# RMR-AVR-ISP-Shield.net
KiCad netlist of a schematic drawn in EAGLE
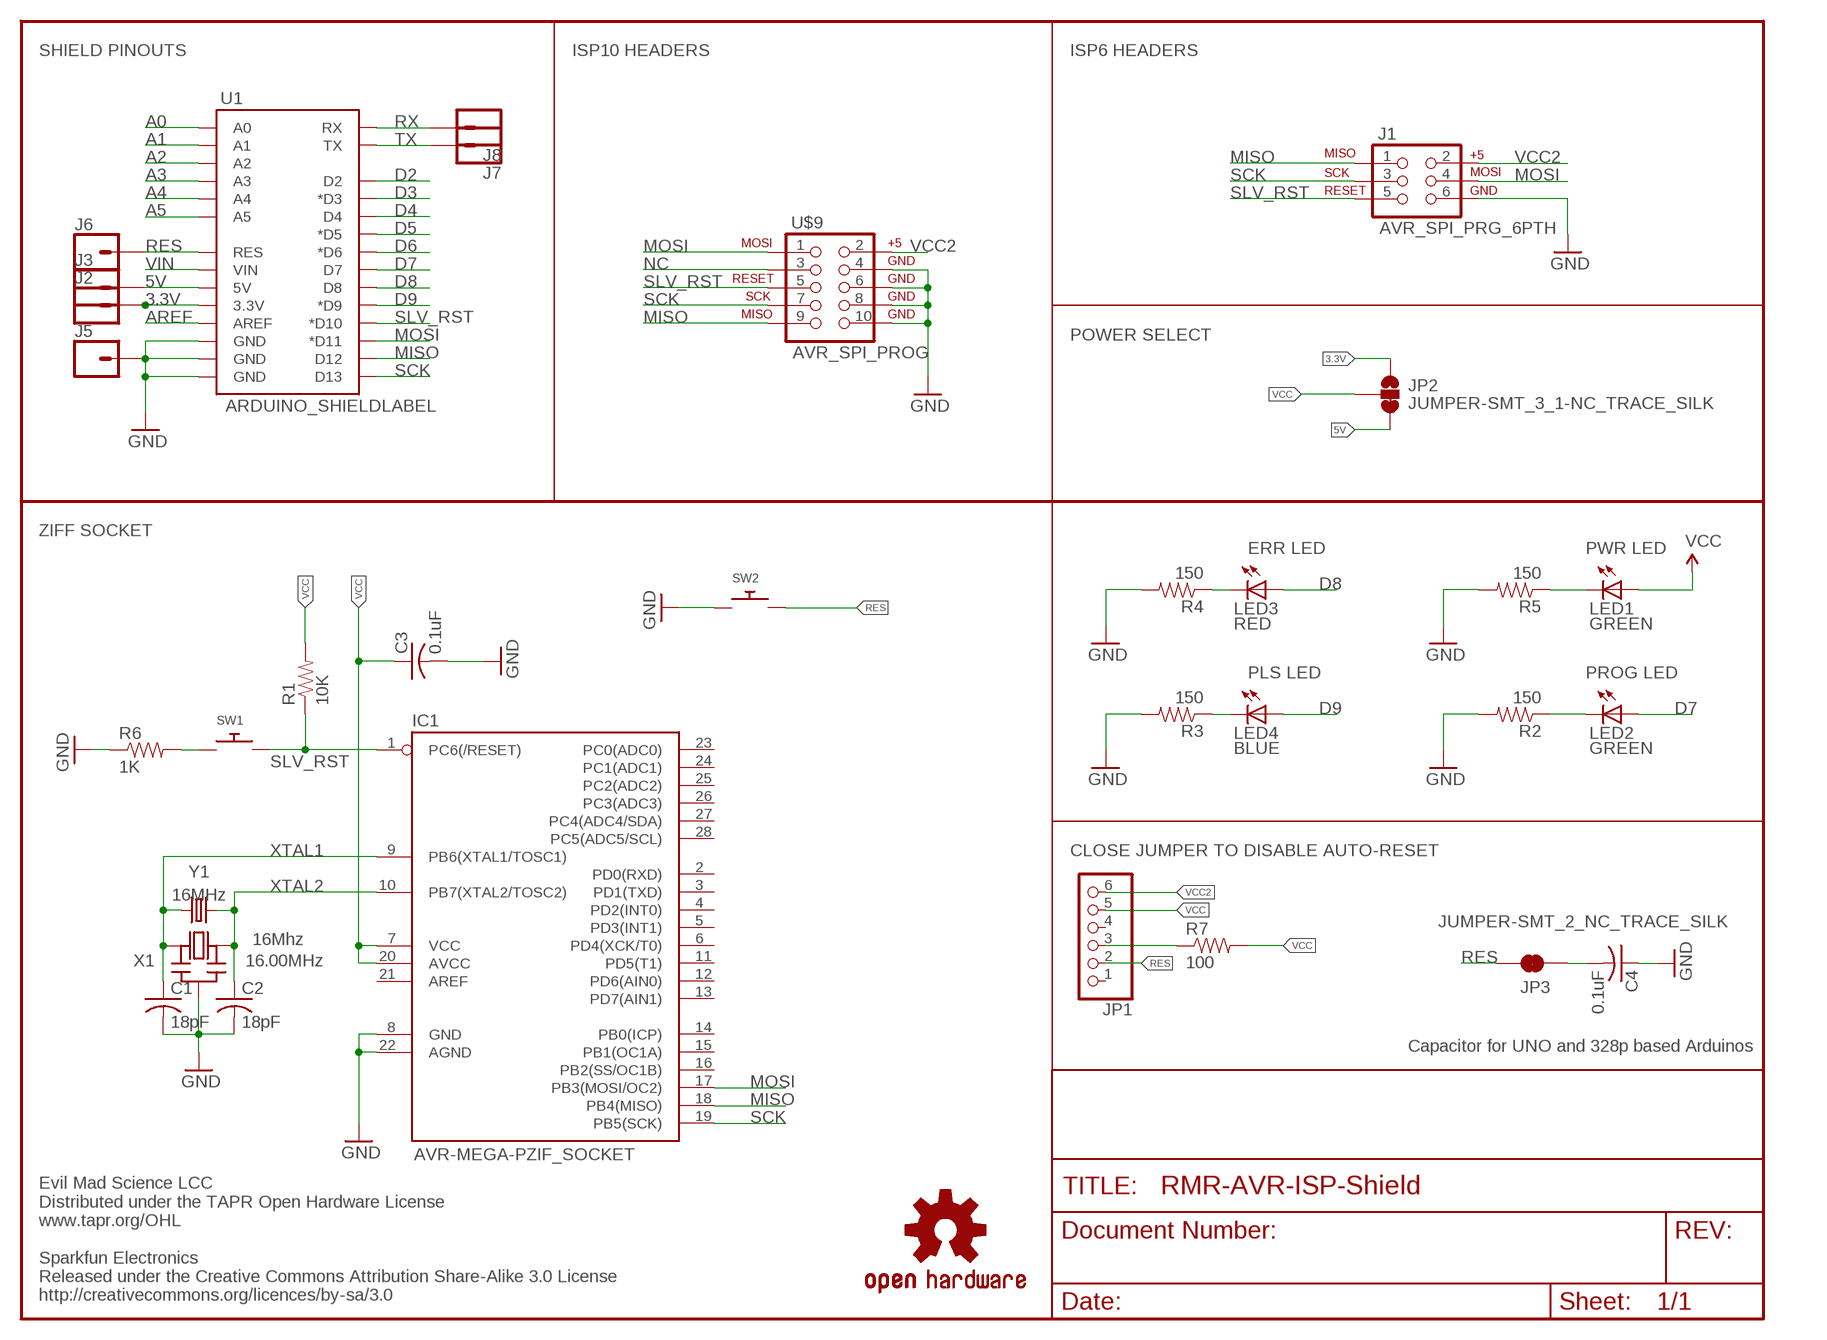
[diagram p0: schematic, sheet 1]

(export (version "E")
  (design (tool "Eeschema 10.0.6"))
  (components
    (comp (ref "C1")
      (value "18pF")
      (footprint "eagle-import:C025-024X044")
      (libsource (lib "eagle-import") (part "C-US025-024X044"))
    )
    (comp (ref "C2")
      (value "18pF")
      (footprint "eagle-import:C025-024X044")
      (libsource (lib "eagle-import") (part "C-US025-024X044"))
    )
    (comp (ref "C3")
      (value "0.1uF")
      (footprint "eagle-import:C025-024X044")
      (libsource (lib "eagle-import") (part "C-US025-024X044"))
    )
    (comp (ref "C4")
      (value "0.1uF")
      (footprint "eagle-import:C025-024X044")
      (libsource (lib "eagle-import") (part "C-US025-024X044"))
    )
    (comp (ref "IC1")
      (value "AVR-MEGA-PZIF_SOCKET")
      (footprint "eagle-import:DIL28-3-ZIF_SOCKET")
      (libsource (lib "eagle-import") (part "AVR-MEGA8-PZIF_SOCKET"))
    )
    (comp (ref "J1")
      (value "AVR_SPI_PRG_6PTH")
      (footprint "eagle-import:2X3")
      (libsource (lib "eagle-import") (part "AVR_SPI_PRG_6PTH"))
    )
    (comp (ref "J2")
      (value "CONN_01")
      (footprint "eagle-import:1X01")
      (libsource (lib "eagle-import") (part "CONN_01"))
    )
    (comp (ref "J3")
      (value "CONN_01")
      (footprint "eagle-import:1X01")
      (libsource (lib "eagle-import") (part "CONN_01"))
    )
    (comp (ref "J5")
      (value "CONN_01")
      (footprint "eagle-import:1X01")
      (libsource (lib "eagle-import") (part "CONN_01"))
    )
    (comp (ref "J6")
      (value "CONN_01")
      (footprint "eagle-import:1X01")
      (libsource (lib "eagle-import") (part "CONN_01"))
    )
    (comp (ref "J7")
      (value "CONN_01")
      (footprint "eagle-import:1X01")
      (libsource (lib "eagle-import") (part "CONN_01"))
    )
    (comp (ref "J8")
      (value "CONN_01")
      (footprint "eagle-import:1X01")
      (libsource (lib "eagle-import") (part "CONN_01"))
    )
    (comp (ref "JP1")
      (value "PINHD-1X6/90")
      (footprint "eagle-import:1X06_90")
      (libsource (lib "eagle-import") (part "PINHD-1X6/90"))
    )
    (comp (ref "JP2")
      (value "JUMPER-SMT_3_1-NC_TRACE_SILK")
      (footprint "eagle-import:SMT-JUMPER_3_1-NC_TRACE_SILK")
      (libsource (lib "eagle-import") (part "JUMPER-SMT_3_1-NC_TRACE_SILK"))
    )
    (comp (ref "JP3")
      (value "JUMPER-SMT_2_NC_TRACE_SILK")
      (footprint "eagle-import:SMT-JUMPER_2_NC_TRACE_SILK")
      (libsource (lib "eagle-import") (part "JUMPER-SMT_2_NC_TRACE_SILK"))
    )
    (comp (ref "LED1")
      (value "GREEN")
      (footprint "eagle-import:LED3MM")
      (libsource (lib "eagle-import") (part "LED3MM"))
    )
    (comp (ref "LED2")
      (value "GREEN")
      (footprint "eagle-import:LED3MM")
      (libsource (lib "eagle-import") (part "LED3MM"))
    )
    (comp (ref "LED3")
      (value "RED")
      (footprint "eagle-import:LED3MM")
      (libsource (lib "eagle-import") (part "LED3MM"))
    )
    (comp (ref "LED4")
      (value "BLUE")
      (footprint "eagle-import:LED3MM")
      (libsource (lib "eagle-import") (part "LED3MM"))
    )
    (comp (ref "R1")
      (value "10K")
      (footprint "eagle-import:AXIAL-0.4")
      (libsource (lib "eagle-import") (part "RESISTORPTH-1/4W"))
    )
    (comp (ref "R2")
      (value "150")
      (footprint "eagle-import:AXIAL-0.4")
      (libsource (lib "eagle-import") (part "RESISTORPTH-1/4W"))
    )
    (comp (ref "R3")
      (value "150")
      (footprint "eagle-import:AXIAL-0.4")
      (libsource (lib "eagle-import") (part "RESISTORPTH-1/4W"))
    )
    (comp (ref "R4")
      (value "150")
      (footprint "eagle-import:AXIAL-0.4")
      (libsource (lib "eagle-import") (part "RESISTORPTH-1/4W"))
    )
    (comp (ref "R5")
      (value "150")
      (footprint "eagle-import:AXIAL-0.4")
      (libsource (lib "eagle-import") (part "RESISTORPTH-1/4W"))
    )
    (comp (ref "R6")
      (value "1K")
      (footprint "eagle-import:AXIAL-0.4")
      (libsource (lib "eagle-import") (part "RESISTORPTH-1/4W"))
    )
    (comp (ref "R7")
      (value "100")
      (footprint "eagle-import:AXIAL-0.4")
      (libsource (lib "eagle-import") (part "RESISTORPTH-1/4W"))
    )
    (comp (ref "SW1")
      (value "SWITCH_PUSHBUTTONEVQ-PE")
      (footprint "eagle-import:TACT_PANA-EVQ")
      (libsource (lib "eagle-import") (part "SWITCH_PUSHBUTTONEVQ-PE"))
    )
    (comp (ref "SW2")
      (value "SWITCH_PUSHBUTTONEVQ-PE")
      (footprint "eagle-import:TACT_PANA-EVQ")
      (libsource (lib "eagle-import") (part "SWITCH_PUSHBUTTONEVQ-PE"))
    )
    (comp (ref "U$4")
      (value "OSHW-LOGOM")
      (footprint "eagle-import:OSHW-LOGO-M")
      (libsource (lib "eagle-import") (part "OSHW-LOGOM"))
    )
    (comp (ref "U$9")
      (value "AVR_SPI_PROG")
      (footprint "eagle-import:AVR_ICSP")
      (libsource (lib "eagle-import") (part "AVR_SPI_PROG"))
    )
    (comp (ref "U1")
      (value "ARDUINO_SHIELDLABEL")
      (footprint "eagle-import:DUEMILANOVE_SHIELD")
      (libsource (lib "eagle-import") (part "ARDUINO_SHIELDLABEL"))
    )
    (comp (ref "X1")
      (value "16.00MHz")
      (footprint "eagle-import:CERM_OSC")
      (libsource (lib "eagle-import") (part "CERMOSCILL"))
    )
    (comp (ref "Y1")
      (value "16MHz")
      (footprint "eagle-import:HC49US")
      (libsource (lib "eagle-import") (part "CRYSTAL-16MHZPTH-HC49US"))
    )
  )
  (nets
    (net (code "1") (name "/A0") (class "Default")
      (node (ref "U1") (pin "A0") (pinfunction "A0_A0") (pintype "bidirectional"))
    )
    (net (code "2") (name "/A1") (class "Default")
      (node (ref "U1") (pin "A1") (pinfunction "A1_A1") (pintype "bidirectional"))
    )
    (net (code "3") (name "/A2") (class "Default")
      (node (ref "U1") (pin "A2") (pinfunction "A2_A2") (pintype "bidirectional"))
    )
    (net (code "4") (name "/A3") (class "Default")
      (node (ref "U1") (pin "A3") (pinfunction "A3_A3") (pintype "bidirectional"))
    )
    (net (code "5") (name "/A4") (class "Default")
      (node (ref "U1") (pin "A4") (pinfunction "A4_A4") (pintype "bidirectional"))
    )
    (net (code "6") (name "/A5") (class "Default")
      (node (ref "U1") (pin "A5") (pinfunction "A5_A5") (pintype "bidirectional"))
    )
    (net (code "7") (name "/AREF") (class "Default")
      (node (ref "U1") (pin "AREF") (pinfunction "AREF_AREF") (pintype "bidirectional"))
    )
    (net (code "8") (name "/D2") (class "Default")
      (node (ref "U1") (pin "D2") (pinfunction "D2_D2") (pintype "bidirectional"))
    )
    (net (code "9") (name "/D3") (class "Default")
      (node (ref "U1") (pin "D3") (pinfunction "*D3_D3") (pintype "bidirectional"))
    )
    (net (code "10") (name "/D4") (class "Default")
      (node (ref "U1") (pin "D4") (pinfunction "D4_D4") (pintype "bidirectional"))
    )
    (net (code "11") (name "/D5") (class "Default")
      (node (ref "U1") (pin "D5") (pinfunction "*D5_D5") (pintype "bidirectional"))
    )
    (net (code "12") (name "/D6") (class "Default")
      (node (ref "U1") (pin "D6") (pinfunction "*D6_D6") (pintype "bidirectional"))
    )
    (net (code "13") (name "/D7") (class "Default")
      (node (ref "LED2") (pin "A") (pinfunction "A_A") (pintype "passive"))
      (node (ref "U1") (pin "D7") (pinfunction "D7_D7") (pintype "bidirectional"))
    )
    (net (code "14") (name "/D8") (class "Default")
      (node (ref "LED3") (pin "A") (pinfunction "A_A") (pintype "passive"))
      (node (ref "U1") (pin "D8") (pinfunction "D8_D8") (pintype "bidirectional"))
    )
    (net (code "15") (name "/D9") (class "Default")
      (node (ref "LED4") (pin "A") (pinfunction "A_A") (pintype "passive"))
      (node (ref "U1") (pin "D9") (pinfunction "*D9_D9") (pintype "bidirectional"))
    )
    (net (code "16") (name "/MISO") (class "Default")
      (node (ref "IC1") (pin "18") (pinfunction "PB4(MISO)_18") (pintype "bidirectional"))
      (node (ref "J1") (pin "1") (pinfunction "1_1") (pintype "passive"))
      (node (ref "U$9") (pin "9") (pinfunction "9_9") (pintype "passive"))
      (node (ref "U1") (pin "D12") (pinfunction "D12_D12") (pintype "bidirectional"))
    )
    (net (code "17") (name "/MOSI") (class "Default")
      (node (ref "IC1") (pin "17") (pinfunction "PB3(MOSI/OC2)_17") (pintype "bidirectional"))
      (node (ref "J1") (pin "4") (pinfunction "4_4") (pintype "passive"))
      (node (ref "U$9") (pin "1") (pinfunction "1_1") (pintype "passive"))
      (node (ref "U1") (pin "D11") (pinfunction "*D11_D11") (pintype "bidirectional"))
    )
    (net (code "18") (name "/NC") (class "Default")
      (node (ref "U$9") (pin "3") (pinfunction "3_3") (pintype "passive"))
    )
    (net (code "19") (name "/RX") (class "Default")
      (node (ref "J8") (pin "1") (pinfunction "1_1") (pintype "passive"))
      (node (ref "U1") (pin "RX") (pinfunction "RX_RX") (pintype "bidirectional"))
    )
    (net (code "20") (name "/SCK") (class "Default")
      (node (ref "IC1") (pin "19") (pinfunction "PB5(SCK)_19") (pintype "bidirectional"))
      (node (ref "J1") (pin "3") (pinfunction "3_3") (pintype "passive"))
      (node (ref "U$9") (pin "7") (pinfunction "7_7") (pintype "passive"))
      (node (ref "U1") (pin "D13") (pinfunction "D13_D13") (pintype "bidirectional"))
    )
    (net (code "21") (name "/SLV_RST") (class "Default")
      (node (ref "IC1") (pin "1") (pinfunction "PC6(/RESET)_1") (pintype "bidirectional"))
      (node (ref "J1") (pin "5") (pinfunction "5_5") (pintype "passive"))
      (node (ref "R1") (pin "P$1") (pinfunction "1_P$1") (pintype "passive"))
      (node (ref "SW1") (pin "P$2") (pinfunction "P$2_P$2") (pintype "passive"))
      (node (ref "U$9") (pin "5") (pinfunction "5_5") (pintype "passive"))
      (node (ref "U1") (pin "D10") (pinfunction "*D10_D10") (pintype "bidirectional"))
    )
    (net (code "22") (name "/TX") (class "Default")
      (node (ref "J7") (pin "1") (pinfunction "1_1") (pintype "passive"))
      (node (ref "U1") (pin "TX") (pinfunction "TX_TX") (pintype "bidirectional"))
    )
    (net (code "23") (name "/VIN") (class "Default")
      (node (ref "U1") (pin "VIN") (pinfunction "VIN_VIN") (pintype "bidirectional"))
    )
    (net (code "24") (name "/XTAL1") (class "Default")
      (node (ref "C1") (pin "1") (pinfunction "1_1") (pintype "passive"))
      (node (ref "IC1") (pin "9") (pinfunction "PB6(XTAL1/TOSC1)_9") (pintype "bidirectional"))
      (node (ref "X1") (pin "P$1") (pinfunction "IN_P$1") (pintype "bidirectional"))
      (node (ref "Y1") (pin "1") (pinfunction "1_1") (pintype "passive"))
    )
    (net (code "25") (name "/XTAL2") (class "Default")
      (node (ref "C2") (pin "1") (pinfunction "1_1") (pintype "passive"))
      (node (ref "IC1") (pin "10") (pinfunction "PB7(XTAL2/TOSC2)_10") (pintype "bidirectional"))
      (node (ref "X1") (pin "P$3") (pinfunction "OUT_P$3") (pintype "bidirectional"))
      (node (ref "Y1") (pin "2") (pinfunction "2_2") (pintype "passive"))
    )
    (net (code "26") (name "3.3V") (class "Default")
      (node (ref "J2") (pin "1") (pinfunction "1_1") (pintype "passive"))
      (node (ref "JP2") (pin "1") (pinfunction "1_1") (pintype "passive"))
      (node (ref "U1") (pin "3.3V") (pinfunction "3.3V_3.3V") (pintype "bidirectional"))
    )
    (net (code "27") (name "5V") (class "Default")
      (node (ref "J3") (pin "1") (pinfunction "1_1") (pintype "passive"))
      (node (ref "JP2") (pin "3") (pinfunction "3_3") (pintype "passive"))
      (node (ref "U1") (pin "5V") (pinfunction "5V_5V") (pintype "bidirectional"))
    )
    (net (code "28") (name "GND") (class "Default")
      (node (ref "C1") (pin "2") (pinfunction "2_2") (pintype "passive"))
      (node (ref "C2") (pin "2") (pinfunction "2_2") (pintype "passive"))
      (node (ref "C3") (pin "2") (pinfunction "2_2") (pintype "passive"))
      (node (ref "C4") (pin "1") (pinfunction "1_1") (pintype "passive"))
      (node (ref "IC1") (pin "22") (pinfunction "AGND_22") (pintype "bidirectional"))
      (node (ref "IC1") (pin "8") (pinfunction "GND_8") (pintype "bidirectional"))
      (node (ref "J1") (pin "6") (pinfunction "6_6") (pintype "passive"))
      (node (ref "J5") (pin "1") (pinfunction "1_1") (pintype "passive"))
      (node (ref "R2") (pin "P$2") (pinfunction "2_P$2") (pintype "passive"))
      (node (ref "R3") (pin "P$2") (pinfunction "2_P$2") (pintype "passive"))
      (node (ref "R4") (pin "P$2") (pinfunction "2_P$2") (pintype "passive"))
      (node (ref "R5") (pin "P$2") (pinfunction "2_P$2") (pintype "passive"))
      (node (ref "R6") (pin "P$1") (pinfunction "1_P$1") (pintype "passive"))
      (node (ref "SW2") (pin "P$1") (pinfunction "P$1_P$1") (pintype "passive"))
      (node (ref "U$9") (pin "10") (pinfunction "10_10") (pintype "passive"))
      (node (ref "U$9") (pin "4") (pinfunction "4_4") (pintype "passive"))
      (node (ref "U$9") (pin "6") (pinfunction "6_6") (pintype "passive"))
      (node (ref "U$9") (pin "8") (pinfunction "8_8") (pintype "passive"))
      (node (ref "U1") (pin "GND@0") (pinfunction "GND_GND@0") (pintype "bidirectional"))
      (node (ref "U1") (pin "GND@1") (pinfunction "GND_GND@1") (pintype "bidirectional"))
      (node (ref "U1") (pin "GND@2") (pinfunction "GND_GND@2") (pintype "bidirectional"))
      (node (ref "X1") (pin "P$2") (pinfunction "GND_P$2") (pintype "bidirectional"))
    )
    (net (code "29") (name "Net-(C4-Pad2)") (class "Default")
      (node (ref "C4") (pin "2") (pinfunction "2_2") (pintype "passive"))
      (node (ref "JP3") (pin "1") (pinfunction "1_1") (pintype "passive"))
    )
    (net (code "30") (name "Net-(LED1-C)") (class "Default")
      (node (ref "LED1") (pin "K") (pinfunction "C_K") (pintype "passive"))
      (node (ref "R5") (pin "P$1") (pinfunction "1_P$1") (pintype "passive"))
    )
    (net (code "31") (name "Net-(LED2-C)") (class "Default")
      (node (ref "LED2") (pin "K") (pinfunction "C_K") (pintype "passive"))
      (node (ref "R2") (pin "P$1") (pinfunction "1_P$1") (pintype "passive"))
    )
    (net (code "32") (name "Net-(LED3-C)") (class "Default")
      (node (ref "LED3") (pin "K") (pinfunction "C_K") (pintype "passive"))
      (node (ref "R4") (pin "P$1") (pinfunction "1_P$1") (pintype "passive"))
    )
    (net (code "33") (name "Net-(LED4-C)") (class "Default")
      (node (ref "LED4") (pin "K") (pinfunction "C_K") (pintype "passive"))
      (node (ref "R3") (pin "P$1") (pinfunction "1_P$1") (pintype "passive"))
    )
    (net (code "34") (name "Net-(R6-2)") (class "Default")
      (node (ref "R6") (pin "P$2") (pinfunction "2_P$2") (pintype "passive"))
      (node (ref "SW1") (pin "P$1") (pinfunction "P$1_P$1") (pintype "passive"))
    )
    (net (code "35") (name "Net-(R7-1)") (class "Default")
      (node (ref "JP1") (pin "3") (pinfunction "3_3") (pintype "passive"))
      (node (ref "R7") (pin "P$1") (pinfunction "1_P$1") (pintype "passive"))
    )
    (net (code "36") (name "RES") (class "Default")
      (node (ref "J6") (pin "1") (pinfunction "1_1") (pintype "passive"))
      (node (ref "JP1") (pin "2") (pinfunction "2_2") (pintype "passive"))
      (node (ref "JP3") (pin "2") (pinfunction "2_2") (pintype "passive"))
      (node (ref "SW2") (pin "P$2") (pinfunction "P$2_P$2") (pintype "passive"))
      (node (ref "U1") (pin "RES") (pinfunction "RES_RES") (pintype "bidirectional"))
    )
    (net (code "37") (name "VCC") (class "Default")
      (node (ref "C3") (pin "1") (pinfunction "1_1") (pintype "passive"))
      (node (ref "IC1") (pin "20") (pinfunction "AVCC_20") (pintype "bidirectional"))
      (node (ref "IC1") (pin "7") (pinfunction "VCC_7") (pintype "bidirectional"))
      (node (ref "JP1") (pin "5") (pinfunction "5_5") (pintype "passive"))
      (node (ref "JP2") (pin "2") (pinfunction "2_2") (pintype "passive"))
      (node (ref "LED1") (pin "A") (pinfunction "A_A") (pintype "passive"))
      (node (ref "R1") (pin "P$2") (pinfunction "2_P$2") (pintype "passive"))
      (node (ref "R7") (pin "P$2") (pinfunction "2_P$2") (pintype "passive"))
    )
    (net (code "38") (name "VCC2") (class "Default")
      (node (ref "J1") (pin "2") (pinfunction "2_2") (pintype "passive"))
      (node (ref "JP1") (pin "6") (pinfunction "6_6") (pintype "passive"))
      (node (ref "U$9") (pin "2") (pinfunction "2_2") (pintype "passive"))
    )
    (net (code "39") (name "unconnected-(IC1-AREF-Pad21)") (class "Default")
      (node (ref "IC1") (pin "21") (pinfunction "AREF_21") (pintype "bidirectional"))
    )
    (net (code "40") (name "unconnected-(IC1-PB0(ICP)-Pad14)") (class "Default")
      (node (ref "IC1") (pin "14") (pinfunction "PB0(ICP)_14") (pintype "bidirectional"))
    )
    (net (code "41") (name "unconnected-(IC1-PB1(OC1A)-Pad15)") (class "Default")
      (node (ref "IC1") (pin "15") (pinfunction "PB1(OC1A)_15") (pintype "bidirectional"))
    )
    (net (code "42") (name "unconnected-(IC1-PB2(SS{slash}OC1B)-Pad16)") (class "Default")
      (node (ref "IC1") (pin "16") (pinfunction "PB2(SS/OC1B)_16") (pintype "bidirectional"))
    )
    (net (code "43") (name "unconnected-(IC1-PC0(ADC0)-Pad23)") (class "Default")
      (node (ref "IC1") (pin "23") (pinfunction "PC0(ADC0)_23") (pintype "bidirectional"))
    )
    (net (code "44") (name "unconnected-(IC1-PC1(ADC1)-Pad24)") (class "Default")
      (node (ref "IC1") (pin "24") (pinfunction "PC1(ADC1)_24") (pintype "bidirectional"))
    )
    (net (code "45") (name "unconnected-(IC1-PC2(ADC2)-Pad25)") (class "Default")
      (node (ref "IC1") (pin "25") (pinfunction "PC2(ADC2)_25") (pintype "bidirectional"))
    )
    (net (code "46") (name "unconnected-(IC1-PC3(ADC3)-Pad26)") (class "Default")
      (node (ref "IC1") (pin "26") (pinfunction "PC3(ADC3)_26") (pintype "bidirectional"))
    )
    (net (code "47") (name "unconnected-(IC1-PC4(ADC4{slash}SDA)-Pad27)") (class "Default")
      (node (ref "IC1") (pin "27") (pinfunction "PC4(ADC4/SDA)_27") (pintype "bidirectional"))
    )
    (net (code "48") (name "unconnected-(IC1-PC5(ADC5{slash}SCL)-Pad28)") (class "Default")
      (node (ref "IC1") (pin "28") (pinfunction "PC5(ADC5/SCL)_28") (pintype "bidirectional"))
    )
    (net (code "49") (name "unconnected-(IC1-PD0(RXD)-Pad2)") (class "Default")
      (node (ref "IC1") (pin "2") (pinfunction "PD0(RXD)_2") (pintype "bidirectional"))
    )
    (net (code "50") (name "unconnected-(IC1-PD1(TXD)-Pad3)") (class "Default")
      (node (ref "IC1") (pin "3") (pinfunction "PD1(TXD)_3") (pintype "bidirectional"))
    )
    (net (code "51") (name "unconnected-(IC1-PD2(INT0)-Pad4)") (class "Default")
      (node (ref "IC1") (pin "4") (pinfunction "PD2(INT0)_4") (pintype "bidirectional"))
    )
    (net (code "52") (name "unconnected-(IC1-PD3(INT1)-Pad5)") (class "Default")
      (node (ref "IC1") (pin "5") (pinfunction "PD3(INT1)_5") (pintype "bidirectional"))
    )
    (net (code "53") (name "unconnected-(IC1-PD4(XCK{slash}T0)-Pad6)") (class "Default")
      (node (ref "IC1") (pin "6") (pinfunction "PD4(XCK/T0)_6") (pintype "bidirectional"))
    )
    (net (code "54") (name "unconnected-(IC1-PD5(T1)-Pad11)") (class "Default")
      (node (ref "IC1") (pin "11") (pinfunction "PD5(T1)_11") (pintype "bidirectional"))
    )
    (net (code "55") (name "unconnected-(IC1-PD6(AIN0)-Pad12)") (class "Default")
      (node (ref "IC1") (pin "12") (pinfunction "PD6(AIN0)_12") (pintype "bidirectional"))
    )
    (net (code "56") (name "unconnected-(IC1-PD7(AIN1)-Pad13)") (class "Default")
      (node (ref "IC1") (pin "13") (pinfunction "PD7(AIN1)_13") (pintype "bidirectional"))
    )
    (net (code "57") (name "unconnected-(JP1-Pad1)") (class "Default")
      (node (ref "JP1") (pin "1") (pinfunction "1_1") (pintype "passive"))
    )
    (net (code "58") (name "unconnected-(JP1-Pad4)") (class "Default")
      (node (ref "JP1") (pin "4") (pinfunction "4_4") (pintype "passive"))
    )
  )
)
